# act-drive2x2.net
KiCad netlist of a schematic drawn in EAGLE
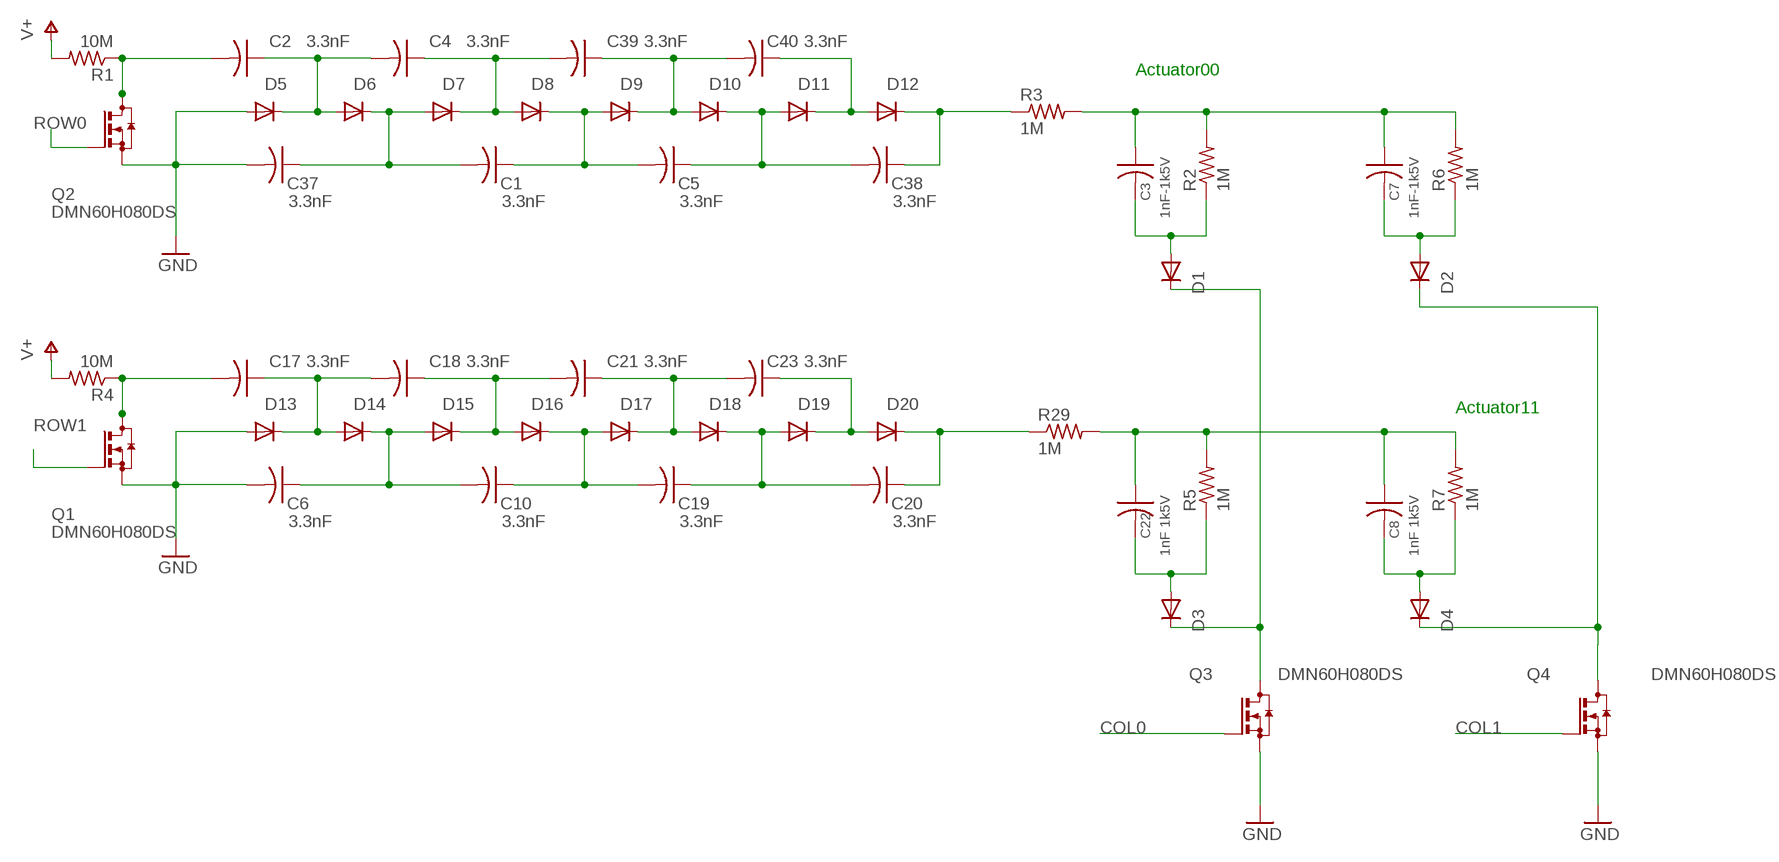
[diagram p0: schematic, sheet 1]

(export (version "E")
  (design (tool "Eeschema 10.0.6"))
  (components
    (comp (ref "C1")
      (value "3.3nF")
      (footprint "eagle-import:C0805K")
      (libsource (lib "eagle-import") (part "rcl_334_C-USC0805K"))
    )
    (comp (ref "C2")
      (value "3.3nF")
      (footprint "eagle-import:C0805K")
      (libsource (lib "eagle-import") (part "rcl_334_C-USC0805K"))
    )
    (comp (ref "C3")
      (value "1nF-1k5V")
      (footprint "eagle-import:C1206")
      (libsource (lib "eagle-import") (part "C-USC1206"))
    )
    (comp (ref "C4")
      (value "3.3nF")
      (footprint "eagle-import:C0805K")
      (libsource (lib "eagle-import") (part "rcl_334_C-USC0805K"))
    )
    (comp (ref "C5")
      (value "3.3nF")
      (footprint "eagle-import:C0805K")
      (libsource (lib "eagle-import") (part "rcl_334_C-USC0805K"))
    )
    (comp (ref "C6")
      (value "3.3nF")
      (footprint "eagle-import:C0805K")
      (libsource (lib "eagle-import") (part "rcl_334_C-USC0805K"))
    )
    (comp (ref "C7")
      (value "1nF-1k5V")
      (footprint "eagle-import:C1206")
      (libsource (lib "eagle-import") (part "C-USC1206"))
    )
    (comp (ref "C8")
      (value "1nF 1k5V")
      (footprint "eagle-import:C1206")
      (libsource (lib "eagle-import") (part "C-USC1206"))
    )
    (comp (ref "C10")
      (value "3.3nF")
      (footprint "eagle-import:C0805K")
      (libsource (lib "eagle-import") (part "rcl_334_C-USC0805K"))
    )
    (comp (ref "C17")
      (value "3.3nF")
      (footprint "eagle-import:C0805K")
      (libsource (lib "eagle-import") (part "rcl_334_C-USC0805K"))
    )
    (comp (ref "C18")
      (value "3.3nF")
      (footprint "eagle-import:C0805K")
      (libsource (lib "eagle-import") (part "rcl_334_C-USC0805K"))
    )
    (comp (ref "C19")
      (value "3.3nF")
      (footprint "eagle-import:C0805K")
      (libsource (lib "eagle-import") (part "rcl_334_C-USC0805K"))
    )
    (comp (ref "C20")
      (value "3.3nF")
      (footprint "eagle-import:C0805K")
      (libsource (lib "eagle-import") (part "rcl_334_C-USC0805K"))
    )
    (comp (ref "C21")
      (value "3.3nF")
      (footprint "eagle-import:C0805K")
      (libsource (lib "eagle-import") (part "rcl_334_C-USC0805K"))
    )
    (comp (ref "C22")
      (value "1nF 1k5V")
      (footprint "eagle-import:C1206")
      (libsource (lib "eagle-import") (part "C-USC1206"))
    )
    (comp (ref "C23")
      (value "3.3nF")
      (footprint "eagle-import:C0805K")
      (libsource (lib "eagle-import") (part "rcl_334_C-USC0805K"))
    )
    (comp (ref "C37")
      (value "3.3nF")
      (footprint "eagle-import:C0805K")
      (libsource (lib "eagle-import") (part "rcl_334_C-USC0805K"))
    )
    (comp (ref "C38")
      (value "3.3nF")
      (footprint "eagle-import:C0805K")
      (libsource (lib "eagle-import") (part "rcl_334_C-USC0805K"))
    )
    (comp (ref "C39")
      (value "3.3nF")
      (footprint "eagle-import:C0805K")
      (libsource (lib "eagle-import") (part "rcl_334_C-USC0805K"))
    )
    (comp (ref "C40")
      (value "3.3nF")
      (footprint "eagle-import:C0805K")
      (libsource (lib "eagle-import") (part "rcl_334_C-USC0805K"))
    )
    (comp (ref "D1")
      (value "DIODE-SOD323-W")
      (footprint "eagle-import:SOD323-W")
      (libsource (lib "eagle-import") (part "DIODE-SOD323-W"))
    )
    (comp (ref "D2")
      (value "DIODE-SOD323-W")
      (footprint "eagle-import:SOD323-W")
      (libsource (lib "eagle-import") (part "DIODE-SOD323-W"))
    )
    (comp (ref "D3")
      (value "DIODE-SOD323-W")
      (footprint "eagle-import:SOD323-W")
      (libsource (lib "eagle-import") (part "DIODE-SOD323-W"))
    )
    (comp (ref "D4")
      (value "DIODE-SOD323-W")
      (footprint "eagle-import:SOD323-W")
      (libsource (lib "eagle-import") (part "DIODE-SOD323-W"))
    )
    (comp (ref "D5")
      (value "DIODE-SOD323-W")
      (footprint "eagle-import:SOD323-W")
      (libsource (lib "eagle-import") (part "DIODE-SOD323-W"))
    )
    (comp (ref "D6")
      (value "DIODE-SOD323-W")
      (footprint "eagle-import:SOD323-W")
      (libsource (lib "eagle-import") (part "DIODE-SOD323-W"))
    )
    (comp (ref "D7")
      (value "DIODE-SOD323-W")
      (footprint "eagle-import:SOD323-W")
      (libsource (lib "eagle-import") (part "DIODE-SOD323-W"))
    )
    (comp (ref "D8")
      (value "DIODE-SOD323-W")
      (footprint "eagle-import:SOD323-W")
      (libsource (lib "eagle-import") (part "DIODE-SOD323-W"))
    )
    (comp (ref "D9")
      (value "DIODE-SOD323-W")
      (footprint "eagle-import:SOD323-W")
      (libsource (lib "eagle-import") (part "DIODE-SOD323-W"))
    )
    (comp (ref "D10")
      (value "DIODE-SOD323-W")
      (footprint "eagle-import:SOD323-W")
      (libsource (lib "eagle-import") (part "DIODE-SOD323-W"))
    )
    (comp (ref "D11")
      (value "DIODE-SOD323-W")
      (footprint "eagle-import:SOD323-W")
      (libsource (lib "eagle-import") (part "DIODE-SOD323-W"))
    )
    (comp (ref "D12")
      (value "DIODE-SOD323-W")
      (footprint "eagle-import:SOD323-W")
      (libsource (lib "eagle-import") (part "DIODE-SOD323-W"))
    )
    (comp (ref "D13")
      (value "DIODE-SOD323-W")
      (footprint "eagle-import:SOD323-W")
      (libsource (lib "eagle-import") (part "DIODE-SOD323-W"))
    )
    (comp (ref "D14")
      (value "DIODE-SOD323-W")
      (footprint "eagle-import:SOD323-W")
      (libsource (lib "eagle-import") (part "DIODE-SOD323-W"))
    )
    (comp (ref "D15")
      (value "DIODE-SOD323-W")
      (footprint "eagle-import:SOD323-W")
      (libsource (lib "eagle-import") (part "DIODE-SOD323-W"))
    )
    (comp (ref "D16")
      (value "DIODE-SOD323-W")
      (footprint "eagle-import:SOD323-W")
      (libsource (lib "eagle-import") (part "DIODE-SOD323-W"))
    )
    (comp (ref "D17")
      (value "DIODE-SOD323-W")
      (footprint "eagle-import:SOD323-W")
      (libsource (lib "eagle-import") (part "DIODE-SOD323-W"))
    )
    (comp (ref "D18")
      (value "DIODE-SOD323-W")
      (footprint "eagle-import:SOD323-W")
      (libsource (lib "eagle-import") (part "DIODE-SOD323-W"))
    )
    (comp (ref "D19")
      (value "DIODE-SOD323-W")
      (footprint "eagle-import:SOD323-W")
      (libsource (lib "eagle-import") (part "DIODE-SOD323-W"))
    )
    (comp (ref "D20")
      (value "DIODE-SOD323-W")
      (footprint "eagle-import:SOD323-W")
      (libsource (lib "eagle-import") (part "DIODE-SOD323-W"))
    )
    (comp (ref "Q1")
      (value "BSS123")
      (footprint "eagle-import:SOT23")
      (fields (field (name "PART#") "DMN60H080DS"))
      (libsource (lib "eagle-import") (part "BSS123"))
    )
    (comp (ref "Q2")
      (value "BSS123")
      (footprint "eagle-import:SOT23")
      (fields (field (name "PART#") "DMN60H080DS"))
      (libsource (lib "eagle-import") (part "BSS123"))
    )
    (comp (ref "Q3")
      (value "BSS123")
      (footprint "eagle-import:SOT23")
      (fields (field (name "PART#") "DMN60H080DS"))
      (libsource (lib "eagle-import") (part "BSS123"))
    )
    (comp (ref "Q4")
      (value "BSS123")
      (footprint "eagle-import:SOT23")
      (fields (field (name "PART#") "DMN60H080DS"))
      (libsource (lib "eagle-import") (part "BSS123"))
    )
    (comp (ref "R1")
      (value "10M")
      (footprint "eagle-import:R1206")
      (libsource (lib "eagle-import") (part "R-US_R1206"))
    )
    (comp (ref "R2")
      (value "1M")
      (footprint "eagle-import:R1206")
      (libsource (lib "eagle-import") (part "R-US_R1206"))
    )
    (comp (ref "R3")
      (value "1M")
      (footprint "eagle-import:R1206")
      (libsource (lib "eagle-import") (part "R-US_R1206"))
    )
    (comp (ref "R4")
      (value "10M")
      (footprint "eagle-import:R1206")
      (libsource (lib "eagle-import") (part "R-US_R1206"))
    )
    (comp (ref "R5")
      (value "1M")
      (footprint "eagle-import:R1206")
      (libsource (lib "eagle-import") (part "R-US_R1206"))
    )
    (comp (ref "R6")
      (value "1M")
      (footprint "eagle-import:R1206")
      (libsource (lib "eagle-import") (part "R-US_R1206"))
    )
    (comp (ref "R7")
      (value "1M")
      (footprint "eagle-import:R1206")
      (libsource (lib "eagle-import") (part "R-US_R1206"))
    )
    (comp (ref "R29")
      (value "1M")
      (footprint "eagle-import:R1206")
      (libsource (lib "eagle-import") (part "R-US_R1206"))
    )
  )
  (nets
    (net (code "1") (name "/COL0") (class "Default")
      (node (ref "Q3") (pin "1") (pinfunction "G_1") (pintype "passive"))
    )
    (net (code "2") (name "/COL1") (class "Default")
      (node (ref "Q4") (pin "1") (pinfunction "G_1") (pintype "passive"))
    )
    (net (code "3") (name "/ROW0") (class "Default")
      (node (ref "Q2") (pin "1") (pinfunction "G_1") (pintype "passive"))
    )
    (net (code "4") (name "/ROW1") (class "Default")
      (node (ref "Q1") (pin "1") (pinfunction "G_1") (pintype "passive"))
    )
    (net (code "5") (name "GND") (class "Default")
      (node (ref "C37") (pin "2") (pinfunction "2_2") (pintype "passive"))
      (node (ref "C6") (pin "2") (pinfunction "2_2") (pintype "passive"))
      (node (ref "D13") (pin "A") (pinfunction "A_A") (pintype "passive"))
      (node (ref "D5") (pin "A") (pinfunction "A_A") (pintype "passive"))
      (node (ref "Q1") (pin "2") (pinfunction "S_2") (pintype "passive"))
      (node (ref "Q2") (pin "2") (pinfunction "S_2") (pintype "passive"))
      (node (ref "Q3") (pin "2") (pinfunction "S_2") (pintype "passive"))
      (node (ref "Q4") (pin "2") (pinfunction "S_2") (pintype "passive"))
    )
    (net (code "6") (name "Net-(C1-Pad1)") (class "Default")
      (node (ref "C1") (pin "1") (pinfunction "1_1") (pintype "passive"))
      (node (ref "C5") (pin "2") (pinfunction "2_2") (pintype "passive"))
      (node (ref "D8") (pin "C") (pinfunction "C_C") (pintype "passive"))
      (node (ref "D9") (pin "A") (pinfunction "A_A") (pintype "passive"))
    )
    (net (code "7") (name "Net-(C1-Pad2)") (class "Default")
      (node (ref "C1") (pin "2") (pinfunction "2_2") (pintype "passive"))
      (node (ref "C37") (pin "1") (pinfunction "1_1") (pintype "passive"))
      (node (ref "D6") (pin "C") (pinfunction "C_C") (pintype "passive"))
      (node (ref "D7") (pin "A") (pinfunction "A_A") (pintype "passive"))
    )
    (net (code "8") (name "Net-(C2-Pad1)") (class "Default")
      (node (ref "C2") (pin "1") (pinfunction "1_1") (pintype "passive"))
      (node (ref "C4") (pin "2") (pinfunction "2_2") (pintype "passive"))
      (node (ref "D5") (pin "C") (pinfunction "C_C") (pintype "passive"))
      (node (ref "D6") (pin "A") (pinfunction "A_A") (pintype "passive"))
    )
    (net (code "9") (name "Net-(C3-Pad1)") (class "Default")
      (node (ref "C3") (pin "1") (pinfunction "1_1") (pintype "passive"))
      (node (ref "C7") (pin "1") (pinfunction "1_1") (pintype "passive"))
      (node (ref "R2") (pin "2") (pinfunction "2_2") (pintype "passive"))
      (node (ref "R3") (pin "2") (pinfunction "2_2") (pintype "passive"))
      (node (ref "R6") (pin "2") (pinfunction "2_2") (pintype "passive"))
    )
    (net (code "10") (name "Net-(C3-Pad2)") (class "Default")
      (node (ref "C3") (pin "2") (pinfunction "2_2") (pintype "passive"))
      (node (ref "D1") (pin "A") (pinfunction "A_A") (pintype "passive"))
      (node (ref "R2") (pin "1") (pinfunction "1_1") (pintype "passive"))
    )
    (net (code "11") (name "Net-(C7-Pad2)") (class "Default")
      (node (ref "C7") (pin "2") (pinfunction "2_2") (pintype "passive"))
      (node (ref "D2") (pin "A") (pinfunction "A_A") (pintype "passive"))
      (node (ref "R6") (pin "1") (pinfunction "1_1") (pintype "passive"))
    )
    (net (code "12") (name "Net-(C8-Pad2)") (class "Default")
      (node (ref "C8") (pin "2") (pinfunction "2_2") (pintype "passive"))
      (node (ref "D4") (pin "A") (pinfunction "A_A") (pintype "passive"))
      (node (ref "R7") (pin "1") (pinfunction "1_1") (pintype "passive"))
    )
    (net (code "13") (name "Net-(C10-Pad1)") (class "Default")
      (node (ref "C10") (pin "1") (pinfunction "1_1") (pintype "passive"))
      (node (ref "C19") (pin "2") (pinfunction "2_2") (pintype "passive"))
      (node (ref "D16") (pin "C") (pinfunction "C_C") (pintype "passive"))
      (node (ref "D17") (pin "A") (pinfunction "A_A") (pintype "passive"))
    )
    (net (code "14") (name "Net-(C10-Pad2)") (class "Default")
      (node (ref "C10") (pin "2") (pinfunction "2_2") (pintype "passive"))
      (node (ref "C6") (pin "1") (pinfunction "1_1") (pintype "passive"))
      (node (ref "D14") (pin "C") (pinfunction "C_C") (pintype "passive"))
      (node (ref "D15") (pin "A") (pinfunction "A_A") (pintype "passive"))
    )
    (net (code "15") (name "Net-(C17-Pad1)") (class "Default")
      (node (ref "C17") (pin "1") (pinfunction "1_1") (pintype "passive"))
      (node (ref "C18") (pin "2") (pinfunction "2_2") (pintype "passive"))
      (node (ref "D13") (pin "C") (pinfunction "C_C") (pintype "passive"))
      (node (ref "D14") (pin "A") (pinfunction "A_A") (pintype "passive"))
    )
    (net (code "16") (name "Net-(C18-Pad1)") (class "Default")
      (node (ref "C18") (pin "1") (pinfunction "1_1") (pintype "passive"))
      (node (ref "C21") (pin "2") (pinfunction "2_2") (pintype "passive"))
      (node (ref "D15") (pin "C") (pinfunction "C_C") (pintype "passive"))
      (node (ref "D16") (pin "A") (pinfunction "A_A") (pintype "passive"))
    )
    (net (code "17") (name "Net-(C19-Pad1)") (class "Default")
      (node (ref "C19") (pin "1") (pinfunction "1_1") (pintype "passive"))
      (node (ref "C20") (pin "2") (pinfunction "2_2") (pintype "passive"))
      (node (ref "D18") (pin "C") (pinfunction "C_C") (pintype "passive"))
      (node (ref "D19") (pin "A") (pinfunction "A_A") (pintype "passive"))
    )
    (net (code "18") (name "Net-(C20-Pad1)") (class "Default")
      (node (ref "C20") (pin "1") (pinfunction "1_1") (pintype "passive"))
      (node (ref "D20") (pin "C") (pinfunction "C_C") (pintype "passive"))
      (node (ref "R29") (pin "1") (pinfunction "1_1") (pintype "passive"))
    )
    (net (code "19") (name "Net-(C21-Pad1)") (class "Default")
      (node (ref "C21") (pin "1") (pinfunction "1_1") (pintype "passive"))
      (node (ref "C23") (pin "2") (pinfunction "2_2") (pintype "passive"))
      (node (ref "D17") (pin "C") (pinfunction "C_C") (pintype "passive"))
      (node (ref "D18") (pin "A") (pinfunction "A_A") (pintype "passive"))
    )
    (net (code "20") (name "Net-(C22-Pad1)") (class "Default")
      (node (ref "C22") (pin "1") (pinfunction "1_1") (pintype "passive"))
      (node (ref "C8") (pin "1") (pinfunction "1_1") (pintype "passive"))
      (node (ref "R29") (pin "2") (pinfunction "2_2") (pintype "passive"))
      (node (ref "R5") (pin "2") (pinfunction "2_2") (pintype "passive"))
      (node (ref "R7") (pin "2") (pinfunction "2_2") (pintype "passive"))
    )
    (net (code "21") (name "Net-(C22-Pad2)") (class "Default")
      (node (ref "C22") (pin "2") (pinfunction "2_2") (pintype "passive"))
      (node (ref "D3") (pin "A") (pinfunction "A_A") (pintype "passive"))
      (node (ref "R5") (pin "1") (pinfunction "1_1") (pintype "passive"))
    )
    (net (code "22") (name "Net-(C23-Pad1)") (class "Default")
      (node (ref "C23") (pin "1") (pinfunction "1_1") (pintype "passive"))
      (node (ref "D19") (pin "C") (pinfunction "C_C") (pintype "passive"))
      (node (ref "D20") (pin "A") (pinfunction "A_A") (pintype "passive"))
    )
    (net (code "23") (name "Net-(C38-Pad1)") (class "Default")
      (node (ref "C38") (pin "1") (pinfunction "1_1") (pintype "passive"))
      (node (ref "D12") (pin "C") (pinfunction "C_C") (pintype "passive"))
      (node (ref "R3") (pin "1") (pinfunction "1_1") (pintype "passive"))
    )
    (net (code "24") (name "Net-(C38-Pad2)") (class "Default")
      (node (ref "C38") (pin "2") (pinfunction "2_2") (pintype "passive"))
      (node (ref "C5") (pin "1") (pinfunction "1_1") (pintype "passive"))
      (node (ref "D10") (pin "C") (pinfunction "C_C") (pintype "passive"))
      (node (ref "D11") (pin "A") (pinfunction "A_A") (pintype "passive"))
    )
    (net (code "25") (name "Net-(C39-Pad1)") (class "Default")
      (node (ref "C39") (pin "1") (pinfunction "1_1") (pintype "passive"))
      (node (ref "C40") (pin "2") (pinfunction "2_2") (pintype "passive"))
      (node (ref "D10") (pin "A") (pinfunction "A_A") (pintype "passive"))
      (node (ref "D9") (pin "C") (pinfunction "C_C") (pintype "passive"))
    )
    (net (code "26") (name "Net-(C39-Pad2)") (class "Default")
      (node (ref "C39") (pin "2") (pinfunction "2_2") (pintype "passive"))
      (node (ref "C4") (pin "1") (pinfunction "1_1") (pintype "passive"))
      (node (ref "D7") (pin "C") (pinfunction "C_C") (pintype "passive"))
      (node (ref "D8") (pin "A") (pinfunction "A_A") (pintype "passive"))
    )
    (net (code "27") (name "Net-(C40-Pad1)") (class "Default")
      (node (ref "C40") (pin "1") (pinfunction "1_1") (pintype "passive"))
      (node (ref "D11") (pin "C") (pinfunction "C_C") (pintype "passive"))
      (node (ref "D12") (pin "A") (pinfunction "A_A") (pintype "passive"))
    )
    (net (code "28") (name "Net-(Q1-D)") (class "Default")
      (node (ref "C17") (pin "2") (pinfunction "2_2") (pintype "passive"))
      (node (ref "Q1") (pin "3") (pinfunction "D_3") (pintype "passive"))
      (node (ref "R4") (pin "1") (pinfunction "1_1") (pintype "passive"))
    )
    (net (code "29") (name "Net-(Q2-D)") (class "Default")
      (node (ref "C2") (pin "2") (pinfunction "2_2") (pintype "passive"))
      (node (ref "Q2") (pin "3") (pinfunction "D_3") (pintype "passive"))
      (node (ref "R1") (pin "1") (pinfunction "1_1") (pintype "passive"))
    )
    (net (code "30") (name "Net-(Q3-D)") (class "Default")
      (node (ref "D1") (pin "C") (pinfunction "C_C") (pintype "passive"))
      (node (ref "D3") (pin "C") (pinfunction "C_C") (pintype "passive"))
      (node (ref "Q3") (pin "3") (pinfunction "D_3") (pintype "passive"))
    )
    (net (code "31") (name "Net-(Q4-D)") (class "Default")
      (node (ref "D2") (pin "C") (pinfunction "C_C") (pintype "passive"))
      (node (ref "D4") (pin "C") (pinfunction "C_C") (pintype "passive"))
      (node (ref "Q4") (pin "3") (pinfunction "D_3") (pintype "passive"))
    )
    (net (code "32") (name "V+") (class "Default")
      (node (ref "R1") (pin "2") (pinfunction "2_2") (pintype "passive"))
      (node (ref "R4") (pin "2") (pinfunction "2_2") (pintype "passive"))
    )
  )
)
